# 03_RPiCM4.net
KiCad netlist of a schematic drawn in Altium Designer
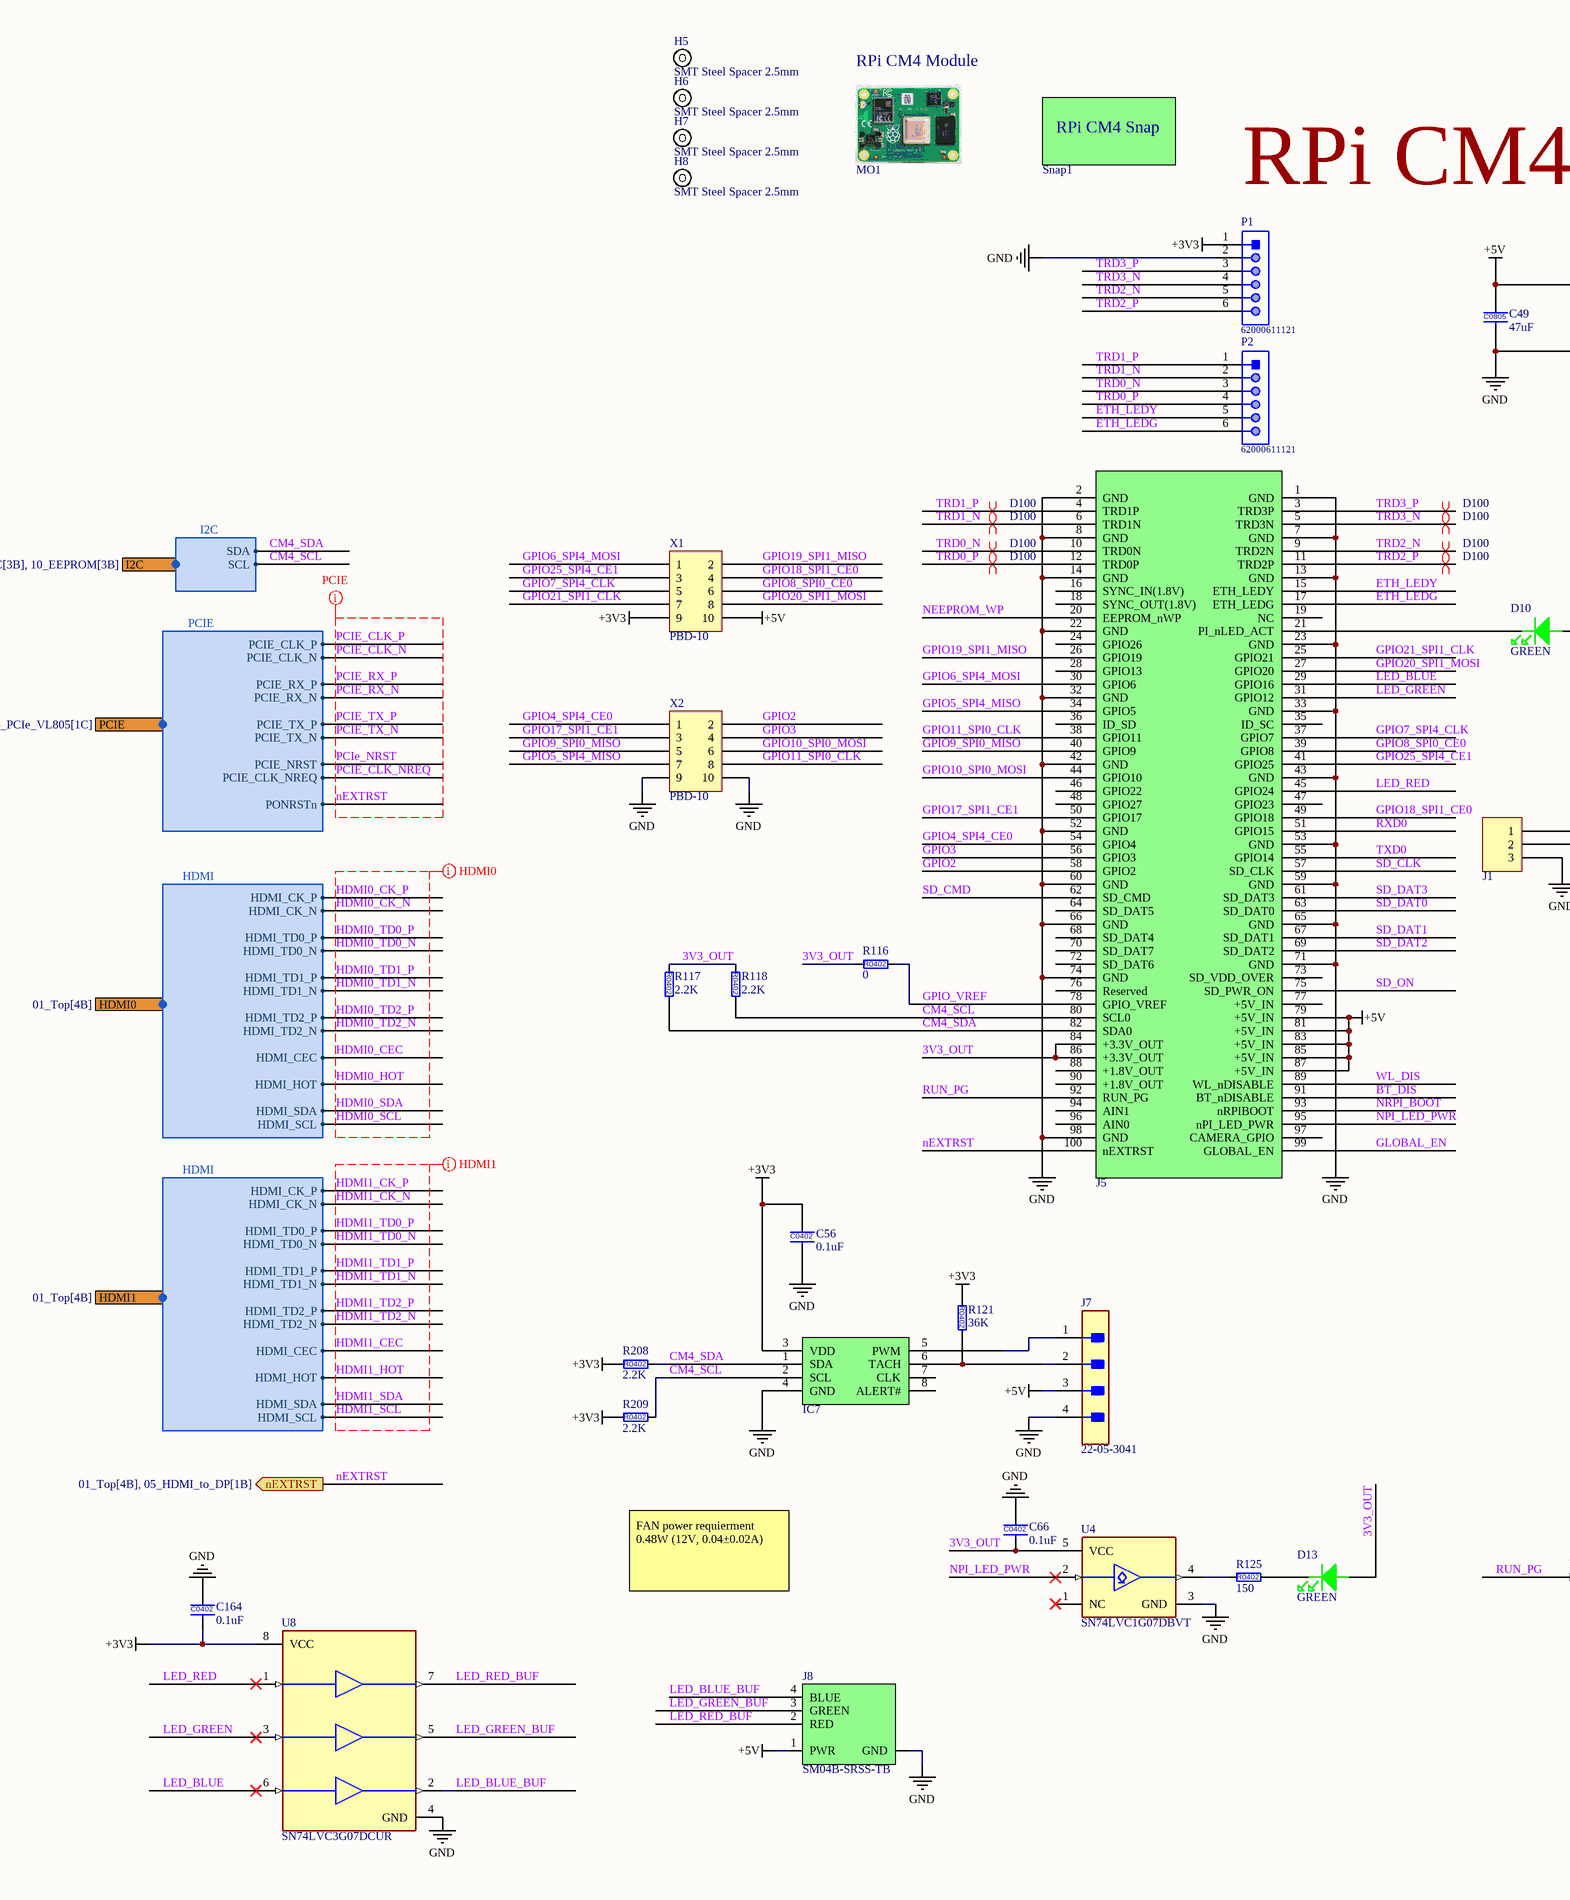
[diagram p0: 03_RPiCM4.SchDoc, left]
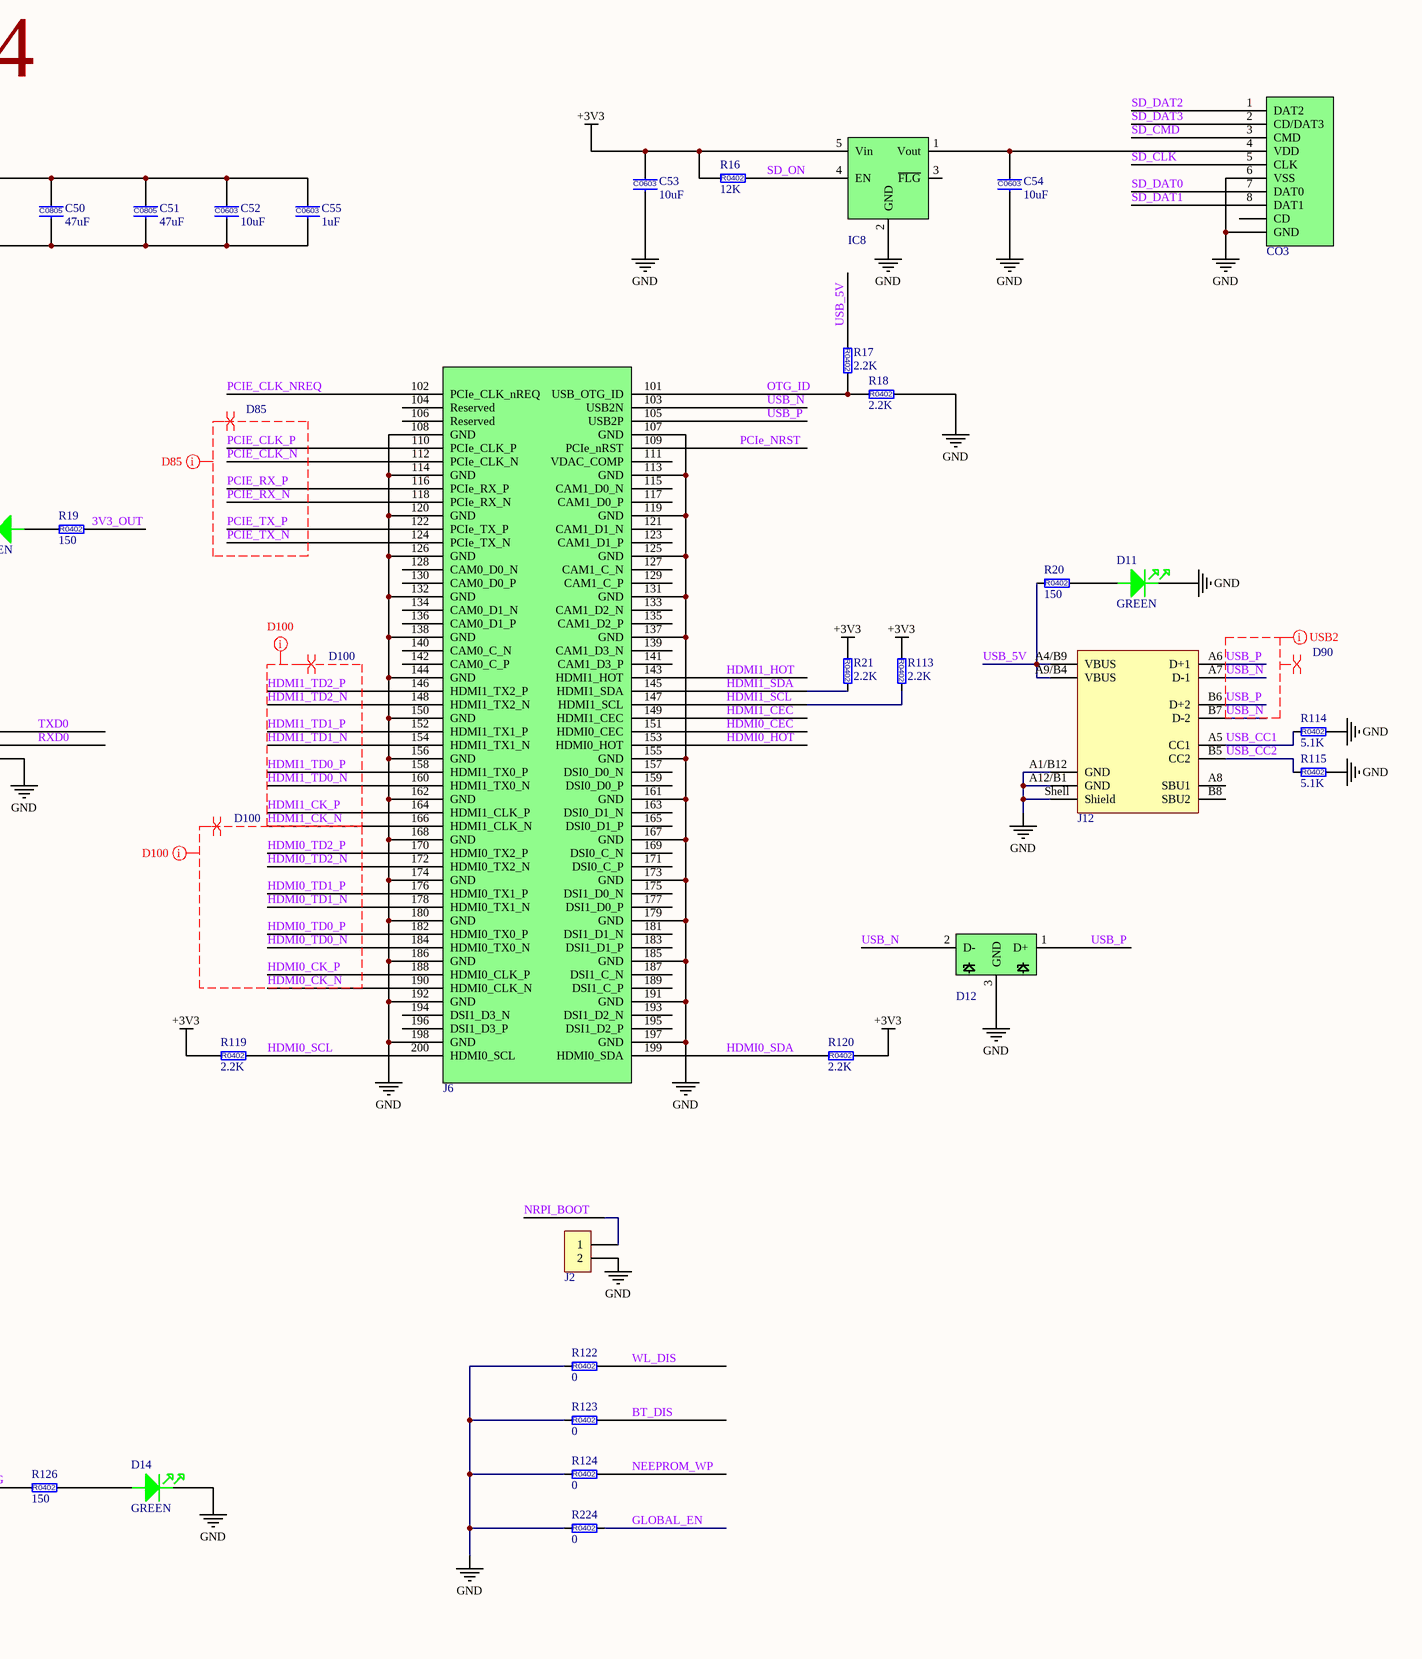
[diagram p1: 03_RPiCM4.SchDoc, right]

(export (version "E")
  (design (tool "Eeschema 10.0.6"))
  (components
    (comp (ref "C49")
      (value "47uF")
      (footprint "C0805")
      (description "CAP CER  47uF 20% 10V X5R 0805")
      (fields
        (field (name "MANUFACTURER") "KYOCERA AVX")
        (field (name "MANUFACTURER PART NUMBER") "0805ZD476MAT2A")
      )
      (libsource (lib "Capacitor") (part "0805ZD476MAT2A"))
    )
    (comp (ref "C50")
      (value "47uF")
      (footprint "C0805")
      (description "CAP CER  47uF 20% 10V X5R 0805")
      (fields
        (field (name "MANUFACTURER") "KYOCERA AVX")
        (field (name "MANUFACTURER PART NUMBER") "0805ZD476MAT2A")
      )
      (libsource (lib "Capacitor") (part "0805ZD476MAT2A"))
    )
    (comp (ref "C51")
      (value "47uF")
      (footprint "C0805")
      (description "CAP CER  47uF 20% 10V X5R 0805")
      (fields
        (field (name "MANUFACTURER") "KYOCERA AVX")
        (field (name "MANUFACTURER PART NUMBER") "0805ZD476MAT2A")
      )
      (libsource (lib "Capacitor") (part "0805ZD476MAT2A"))
    )
    (comp (ref "C52")
      (value "10uF")
      (footprint "C0603")
      (description "CAP CER 10uF 10% 10V X5R 0603")
      (fields
        (field (name "MANUFACTURER") "KYOCERA AVX")
        (field (name "MANUFACTURER PART NUMBER") "0603ZD106KAT2A")
      )
      (libsource (lib "Capacitor") (part "0603ZD106KAT2A"))
    )
    (comp (ref "C53")
      (value "10uF")
      (footprint "C0603")
      (description "CAP CER 10uF 10% 10V X5R 0603")
      (fields
        (field (name "MANUFACTURER") "KYOCERA AVX")
        (field (name "MANUFACTURER PART NUMBER") "0603ZD106KAT2A")
      )
      (libsource (lib "Capacitor") (part "0603ZD106KAT2A"))
    )
    (comp (ref "C54")
      (value "10uF")
      (footprint "C0603")
      (description "CAP CER 10uF 10% 10V X5R 0603")
      (fields
        (field (name "MANUFACTURER") "KYOCERA AVX")
        (field (name "MANUFACTURER PART NUMBER") "0603ZD106KAT2A")
      )
      (libsource (lib "Capacitor") (part "0603ZD106KAT2A"))
    )
    (comp (ref "C55")
      (value "1uF")
      (footprint "C0603")
      (description "CAP CER 1uF 20% 10V X5R 0603")
      (fields (field (name "TOLERANCE") "20%") (field (name "MANUFACTURER") "KYOCERA AVX"))
      (libsource (lib "Capacitor") (part "0201ZD105MAT2A"))
    )
    (comp (ref "C56")
      (value "0.1uF")
      (footprint "C0402")
      (description "CAP CER  0.1uF 10% 25V X5R 0402")
      (fields
        (field (name "MANUFACTURER") "AVX Corporation")
        (field (name "MANUFACTURER PART NUMBER") "04023D104KAT2A")
      )
      (libsource (lib "Capacitor") (part "04023D104KAT2A"))
    )
    (comp (ref "C66")
      (value "0.1uF")
      (footprint "C0402")
      (description "CAP CER  0.1uF 10% 25V X5R 0402")
      (fields
        (field (name "MANUFACTURER") "AVX Corporation")
        (field (name "MANUFACTURER PART NUMBER") "04023D104KAT2A")
      )
      (libsource (lib "Capacitor") (part "04023D104KAT2A"))
    )
    (comp (ref "C164")
      (value "0.1uF")
      (footprint "C0402")
      (description "CAP CER  0.1uF 10% 25V X5R 0402")
      (fields
        (field (name "MANUFACTURER") "AVX Corporation")
        (field (name "MANUFACTURER PART NUMBER") "04023D104KAT2A")
      )
      (libsource (lib "Capacitor") (part "04023D104KAT2A"))
    )
    (comp (ref "CO3")
      (value "µSD-Card")
      (footprint "693071030811")
      (description "Micro Sd Card, Push-Push, 8Pos, Smt Rohs Compliant: Yes")
      (fields (field (name "PART NUMBER") "CO0027") (field (name "MANUFACTURER") "Wurth Electronics"))
      (libsource (lib "new") (part "693071030811"))
    )
    (comp (ref "D10")
      (value "GREEN")
      (footprint "LED_0603")
      (description "LED Uni-Color Yellow Green 574nm 2-Pin Chip 0603(1608Metric) T/R")
      (fields
        (field (name "MANUFACTURER") "Vishay Semiconductors")
        (field (name "MANUFACTURER PART NUMBER") "VLMG1300-GS08")
      )
      (libsource (lib "led") (part "LED_SMD_0603_GREEN"))
    )
    (comp (ref "D11")
      (value "GREEN")
      (footprint "LED_0603")
      (description "LED Uni-Color Yellow Green 574nm 2-Pin Chip 0603(1608Metric) T/R")
      (fields
        (field (name "MANUFACTURER") "Vishay Semiconductors")
        (field (name "MANUFACTURER PART NUMBER") "VLMG1300-GS08")
      )
      (libsource (lib "led") (part "LED_SMD_0603_GREEN"))
    )
    (comp (ref "D12")
      (value "TPD2EUSB30DRTR")
      (footprint "TPD2EUSB30DRTR_SOT-3")
      (fields (field (name "MANUFACTURER") "Texas Instruments"))
      (libsource (lib "new") (part "TPD2EUSB30DRTR"))
    )
    (comp (ref "D13")
      (value "GREEN")
      (footprint "LED_0603")
      (description "LED Uni-Color Yellow Green 574nm 2-Pin Chip 0603(1608Metric) T/R")
      (fields
        (field (name "MANUFACTURER") "Vishay Semiconductors")
        (field (name "MANUFACTURER PART NUMBER") "VLMG1300-GS08")
      )
      (libsource (lib "led") (part "LED_SMD_0603_GREEN"))
    )
    (comp (ref "D14")
      (value "GREEN")
      (footprint "LED_0603")
      (description "LED Uni-Color Yellow Green 574nm 2-Pin Chip 0603(1608Metric) T/R")
      (fields
        (field (name "MANUFACTURER") "Vishay Semiconductors")
        (field (name "MANUFACTURER PART NUMBER") "VLMG1300-GS08")
      )
      (libsource (lib "led") (part "LED_SMD_0603_GREEN"))
    )
    (comp (ref "H5")
      (value "SMT Steel Spacer 2.5mm")
      (description "Spacer Material: Steel Mounting: SMT Series: WA-SMSI Thread D: M2.5")
      (fields
        (field (name "MANUFACTURER") "Wurth Electronics")
        (field (name "MANUFACTURER PART NUMBER") "9774030151R")
      )
      (libsource (lib "mechanical") (part "9774030151R"))
    )
    (comp (ref "H6")
      (value "SMT Steel Spacer 2.5mm")
      (description "Spacer Material: Steel Mounting: SMT Series: WA-SMSI Thread D: M2.5")
      (fields
        (field (name "MANUFACTURER") "Wurth Electronics")
        (field (name "MANUFACTURER PART NUMBER") "9774030151R")
      )
      (libsource (lib "mechanical") (part "9774030151R"))
    )
    (comp (ref "H7")
      (value "SMT Steel Spacer 2.5mm")
      (description "Spacer Material: Steel Mounting: SMT Series: WA-SMSI Thread D: M2.5")
      (fields
        (field (name "MANUFACTURER") "Wurth Electronics")
        (field (name "MANUFACTURER PART NUMBER") "9774030151R")
      )
      (libsource (lib "mechanical") (part "9774030151R"))
    )
    (comp (ref "H8")
      (value "SMT Steel Spacer 2.5mm")
      (description "Spacer Material: Steel Mounting: SMT Series: WA-SMSI Thread D: M2.5")
      (fields
        (field (name "MANUFACTURER") "Wurth Electronics")
        (field (name "MANUFACTURER PART NUMBER") "9774030151R")
      )
      (libsource (lib "mechanical") (part "9774030151R"))
    )
    (comp (ref "IC7")
      (value "EMC2301")
      (footprint "EMC2301-1-ACZL-TR_MSOP-8")
      (description "RPM-BASED PWM FAN CONTROLLER")
      (fields (field (name "PART NUMBER") "IC0054") (field (name "MANFACTPART") "EMC2301-1-ACZL-TR"))
      (libsource (lib "new") (part "EMC2301-1-ACZL-TR"))
    )
    (comp (ref "IC8")
      (value "RT9742")
      (footprint "RT9742GGJ5_SOT_23_5")
      (description "IC Pwr Swtch N-chan 1: 1 TSOT23-5")
      (fields (field (name "PART NUMBER") "IC0029") (field (name "MANFACTPART") "RT9742GGJ5"))
      (libsource (lib "new") (part "RT9742GGJ5"))
    )
    (comp (ref "J1")
      (value "PLS-3")
      (footprint "PLS-3-3D")
      (description "Board to Board Connector Straight Header Single Row 3 Position 2.54mm Pitch Through Hole Bag")
      (fields
        (field (name "MANUFACTURER") "Amphenol")
        (field (name "MANUFACTURER PART NUMBER") "G800W305018EU")
      )
      (libsource (lib "Connector") (part "PLS-3"))
    )
    (comp (ref "J2")
      (value "PLS-2")
      (footprint "PLS-2-3D")
      (description "Pin Header 2.54MM Pitch Str, 1X2PIN, Full G/f, NY6T, 6.1MM*2.5MM*3.0MM / Bag")
      (fields
        (field (name "MANUFACTURER") "Amphenol")
        (field (name "MANUFACTURER PART NUMBER") "G800W306018EU")
      )
      (libsource (lib "Connector") (part "PLS-2"))
    )
    (comp (ref "J5")
      (value "CM4-1")
      (footprint "CM4_CON_A")
      (description "0.4mm Pitch, 1.5-4.0mm Height, Board to Board / FPC to Board Connectors")
      (fields (field (name "PART NUMBER") "MO0012") (field (name "MANFACTPART") "DF40HC(3.0)-100DS-0.4V"))
      (libsource (lib "new") (part "CM4_module_A"))
    )
    (comp (ref "J6")
      (value "CM4-1")
      (footprint "CM4_Con_B")
      (description "0.4mm Pitch, 1.5-4.0mm Height, Board to Board / FPC to Board Connectors")
      (fields (field (name "PART NUMBER") "MO0012") (field (name "MANFACTPART") "DF40HC(3.0)-100DS-0.4V"))
      (libsource (lib "new") (part "CM4_module_B"))
    )
    (comp (ref "J7")
      (value "22-05-3041")
      (footprint "FP-22-05-3041-MFG")
      (description "KK 254 Solid Header, Right-Angle, with Friction Lock, 4 Circuits, Tin (Sn) Plating")
      (fields
        (field (name "OCTOPART") "https://octopart.com/22-05-3041-molex-2579")
        (field (name "MANUFACTURER") "Molex")
      )
      (libsource (lib "new") (part "22-05-3041"))
    )
    (comp (ref "J8")
      (value "SM04B-SRSS-TB")
      (footprint "SM04B")
      (description "CONN HEADER SH 4POS SIDE 1MM TIN")
      (fields (field (name "PART NUMBER") "CO0056") (field (name "MANUFACTURER") "JST"))
      (libsource (lib "new") (part "SM04B-SRSS-TB"))
    )
    (comp (ref "J12")
      (value "USB4105-GF-A")
      (footprint "USB4105-GF-A")
      (description "Conn USB 2.0 Type C RCP 24 POS 0.3mm/0.5mm Solder RA SMD 24 Terminal 1 Port T/R")
      (fields (field (name "MANUFACTURER") "Global Connector Technology"))
      (libsource (lib "new") (part "USB4105-GF-A"))
    )
    (comp (ref "MO1")
      (value "CM4_module")
      (footprint "CM4_step")
      (description "CM4 module")
      (fields (field (name "PART NUMBER") "MO0011") (field (name "MANFACTPART") "RPI CM4"))
      (libsource (lib "new") (part "CM4_module"))
    )
    (comp (ref "P1")
      (value "62000611121")
      (footprint "62000611121")
      (description "THT Vertical Pin Header WR-PHD, Pitch 2.00 mm, Single Row, 6 pins")
      (fields (field (name "MANUFACTURER") "Wurth Elektronik") (field (name "PUBLISHER") "WurthElektronik"))
      (libsource (lib "Pin_header") (part "CMP-1502-00960-1"))
    )
    (comp (ref "P2")
      (value "62000611121")
      (footprint "62000611121")
      (description "THT Vertical Pin Header WR-PHD, Pitch 2.00 mm, Single Row, 6 pins")
      (fields (field (name "MANUFACTURER") "Wurth Elektronik") (field (name "PUBLISHER") "WurthElektronik"))
      (libsource (lib "Pin_header") (part "CMP-1502-00960-1"))
    )
    (comp (ref "R16")
      (value "12K")
      (footprint "R0402")
      (description "RES SMD 12K ohm 1% 1/16W R0402")
      (fields
        (field (name "MANUFACTURER") "Vishay")
        (field (name "MANUFACTURER PART NUMBER") "CRCW040212K0FK")
      )
      (libsource (lib "Resistor") (part "CRCW040212K0FK"))
    )
    (comp (ref "R17")
      (value "2.2K")
      (footprint "R0402")
      (description "RES SMD 2.2K ohm 1% 1/16W R0402")
      (fields
        (field (name "MANUFACTURER") "Vishay")
        (field (name "MANUFACTURER PART NUMBER") "CRCW04022K20FK")
      )
      (libsource (lib "Resistor") (part "CRCW04022K20FK"))
    )
    (comp (ref "R18")
      (value "2.2K")
      (footprint "R0402")
      (description "RES SMD 2.2K ohm 1% 1/16W R0402")
      (fields
        (field (name "MANUFACTURER") "Vishay")
        (field (name "MANUFACTURER PART NUMBER") "CRCW04022K20FK")
      )
      (libsource (lib "Resistor") (part "CRCW04022K20FK"))
    )
    (comp (ref "R19")
      (value "150")
      (footprint "R0402")
      (description "RES SMD 150 ohm 1% 1/16W R0402")
      (fields
        (field (name "MANUFACTURER") "Vishay Dale")
        (field (name "MANUFACTURER PART NUMBER") "CRCW0402150RFKEDC")
      )
      (libsource (lib "Resistor") (part "CRCW0402150RFKEDC"))
    )
    (comp (ref "R20")
      (value "150")
      (footprint "R0402")
      (description "RES SMD 150 ohm 1% 1/16W R0402")
      (fields
        (field (name "MANUFACTURER") "Vishay Dale")
        (field (name "MANUFACTURER PART NUMBER") "CRCW0402150RFKEDC")
      )
      (libsource (lib "Resistor") (part "CRCW0402150RFKEDC"))
    )
    (comp (ref "R21")
      (value "2.2K")
      (footprint "R0402")
      (description "RES SMD 2.2K ohm 1% 1/16W R0402")
      (fields
        (field (name "MANUFACTURER") "Vishay")
        (field (name "MANUFACTURER PART NUMBER") "CRCW04022K20FK")
      )
      (libsource (lib "Resistor") (part "CRCW04022K20FK"))
    )
    (comp (ref "R113")
      (value "2.2K")
      (footprint "R0402")
      (description "RES SMD 2.2K ohm 1% 1/16W R0402")
      (fields
        (field (name "MANUFACTURER") "Vishay")
        (field (name "MANUFACTURER PART NUMBER") "CRCW04022K20FK")
      )
      (libsource (lib "Resistor") (part "CRCW04022K20FK"))
    )
    (comp (ref "R114")
      (value "5.1K")
      (footprint "R0402")
      (description "RES SMD 5.1K ohm 1% 1/16W R0402")
      (fields
        (field (name "MANUFACTURER") "Vishay")
        (field (name "MANUFACTURER PART NUMBER") "CRCW04025K10FK")
      )
      (libsource (lib "Resistor") (part "CRCW04025K10FK"))
    )
    (comp (ref "R115")
      (value "5.1K")
      (footprint "R0402")
      (description "RES SMD 5.1K ohm 1% 1/16W R0402")
      (fields
        (field (name "MANUFACTURER") "Vishay")
        (field (name "MANUFACTURER PART NUMBER") "CRCW04025K10FK")
      )
      (libsource (lib "Resistor") (part "CRCW04025K10FK"))
    )
    (comp (ref "R116")
      (value "0")
      (footprint "R0402")
      (description "RES SMD 0 ohm 1/16W R0402")
      (fields
        (field (name "MANUFACTURER") "Vishay Dale")
        (field (name "MANUFACTURER PART NUMBER") "CRCW04020000Z0")
      )
      (libsource (lib "Resistor") (part "CRCW04020000Z0"))
    )
    (comp (ref "R117")
      (value "2.2K")
      (footprint "R0402")
      (description "RES SMD 2.2K ohm 1% 1/16W R0402")
      (fields
        (field (name "MANUFACTURER") "Vishay")
        (field (name "MANUFACTURER PART NUMBER") "CRCW04022K20FK")
      )
      (libsource (lib "Resistor") (part "CRCW04022K20FK"))
    )
    (comp (ref "R118")
      (value "2.2K")
      (footprint "R0402")
      (description "RES SMD 2.2K ohm 1% 1/16W R0402")
      (fields
        (field (name "MANUFACTURER") "Vishay")
        (field (name "MANUFACTURER PART NUMBER") "CRCW04022K20FK")
      )
      (libsource (lib "Resistor") (part "CRCW04022K20FK"))
    )
    (comp (ref "R119")
      (value "2.2K")
      (footprint "R0402")
      (description "RES SMD 2.2K ohm 1% 1/16W R0402")
      (fields
        (field (name "MANUFACTURER") "Vishay")
        (field (name "MANUFACTURER PART NUMBER") "CRCW04022K20FK")
      )
      (libsource (lib "Resistor") (part "CRCW04022K20FK"))
    )
    (comp (ref "R120")
      (value "2.2K")
      (footprint "R0402")
      (description "RES SMD 2.2K ohm 1% 1/16W R0402")
      (fields
        (field (name "MANUFACTURER") "Vishay")
        (field (name "MANUFACTURER PART NUMBER") "CRCW04022K20FK")
      )
      (libsource (lib "Resistor") (part "CRCW04022K20FK"))
    )
    (comp (ref "R121")
      (value "36K")
      (footprint "R0402")
      (description "RES SMD 36K ohm 1% 1/16W R0402")
      (fields
        (field (name "MANUFACTURER") "Vishay")
        (field (name "MANUFACTURER PART NUMBER") "CRCW040236K0FK")
      )
      (libsource (lib "Resistor") (part "CRCW040236K0FK"))
    )
    (comp (ref "R122")
      (value "0")
      (footprint "R0402")
      (description "RES SMD 0 ohm 1/16W R0402")
      (fields
        (field (name "MANUFACTURER") "Vishay Dale")
        (field (name "MANUFACTURER PART NUMBER") "CRCW04020000Z0")
      )
      (libsource (lib "Resistor") (part "CRCW04020000Z0"))
    )
    (comp (ref "R123")
      (value "0")
      (footprint "R0402")
      (description "RES SMD 0 ohm 1/16W R0402")
      (fields
        (field (name "MANUFACTURER") "Vishay Dale")
        (field (name "MANUFACTURER PART NUMBER") "CRCW04020000Z0")
      )
      (libsource (lib "Resistor") (part "CRCW04020000Z0"))
    )
    (comp (ref "R124")
      (value "0")
      (footprint "R0402")
      (description "RES SMD 0 ohm 1/16W R0402")
      (fields
        (field (name "MANUFACTURER") "Vishay Dale")
        (field (name "MANUFACTURER PART NUMBER") "CRCW04020000Z0")
      )
      (libsource (lib "Resistor") (part "CRCW04020000Z0"))
    )
    (comp (ref "R125")
      (value "150")
      (footprint "R0402")
      (description "RES SMD 150 ohm 1% 1/16W R0402")
      (fields
        (field (name "MANUFACTURER") "Vishay Dale")
        (field (name "MANUFACTURER PART NUMBER") "CRCW0402150RFKEDC")
      )
      (libsource (lib "Resistor") (part "CRCW0402150RFKEDC"))
    )
    (comp (ref "R126")
      (value "150")
      (footprint "R0402")
      (description "RES SMD 150 ohm 1% 1/16W R0402")
      (fields
        (field (name "MANUFACTURER") "Vishay Dale")
        (field (name "MANUFACTURER PART NUMBER") "CRCW0402150RFKEDC")
      )
      (libsource (lib "Resistor") (part "CRCW0402150RFKEDC"))
    )
    (comp (ref "R208")
      (value "2.2K")
      (footprint "R0402")
      (description "RES SMD 2.2K ohm 1% 1/16W R0402")
      (fields
        (field (name "MANUFACTURER") "Vishay")
        (field (name "MANUFACTURER PART NUMBER") "CRCW04022K20FK")
      )
      (libsource (lib "Resistor") (part "CRCW04022K20FK"))
    )
    (comp (ref "R209")
      (value "2.2K")
      (footprint "R0402")
      (description "RES SMD 2.2K ohm 1% 1/16W R0402")
      (fields
        (field (name "MANUFACTURER") "Vishay")
        (field (name "MANUFACTURER PART NUMBER") "CRCW04022K20FK")
      )
      (libsource (lib "Resistor") (part "CRCW04022K20FK"))
    )
    (comp (ref "R224")
      (value "0")
      (footprint "R0402")
      (description "RES SMD 0 ohm 1/16W R0402")
      (fields
        (field (name "MANUFACTURER") "Vishay Dale")
        (field (name "MANUFACTURER PART NUMBER") "CRCW04020000Z0")
      )
      (libsource (lib "Resistor") (part "CRCW04020000Z0"))
    )
    (comp (ref "Snap1")
      (value "CM4-1")
      (footprint "CM4_snap")
      (description "RPI CM4 snap")
      (fields (field (name "PART NUMBER") "MO0012"))
      (libsource (lib "new") (part "CM4_snap"))
    )
    (comp (ref "U4")
      (value "SN74LVC1G07DBVT")
      (footprint "SN74LVC1G07DBVT_SOT_23_5")
      (description "Single 1.65-V to 5.5-V buffer with open-drain outputs 5-SOT-23 -40 to 125")
      (fields
        (field (name "MANUFACTURER") "Texas Instruments")
        (field (name "OCTOPART") "https://octopart.com/sn74lvc1g07dbvt-texas+instruments-1006798")
      )
      (libsource (lib "new") (part "SN74LVC1G07DBVT"))
    )
    (comp (ref "U8")
      (value "SN74LVC3G07DCUR")
      (footprint "SN74LVC3G07DCUR_VSSOP_8")
      (description "Buffer/Driver 3-CH Non-Inverting Open Drain CMOS 8-Pin VSSOP T/R")
      (fields (field (name "MANUFACTURER") "Texas Instruments"))
      (libsource (lib "ic") (part "SN74LVC3G07DCUR"))
    )
    (comp (ref "X1")
      (value "PBD-10")
      (footprint "PXD-10")
      (description "Header, 5-Pin, Dual row")
      (libsource (lib "Connector") (part "PBD-10"))
    )
    (comp (ref "X2")
      (value "PBD-10")
      (footprint "PXD-10")
      (description "Header, 5-Pin, Dual row")
      (libsource (lib "Connector") (part "PBD-10"))
    )
  )
  (nets
    (net (code "4") (name "+3V3") (class "Default")
      (node (ref "C164") (pin "2") (pinfunction "2_2") (pintype "passive"))
      (node (ref "C53") (pin "1") (pinfunction "1_1") (pintype "passive"))
      (node (ref "C56") (pin "1") (pinfunction "1_1") (pintype "passive"))
      (node (ref "IC7") (pin "3") (pinfunction "VDD_3") (pintype "passive"))
      (node (ref "IC8") (pin "5") (pinfunction "Vin_5") (pintype "power_in"))
      (node (ref "P1") (pin "1") (pinfunction "1_1") (pintype "passive"))
      (node (ref "R113") (pin "1") (pinfunction "1_1") (pintype "passive"))
      (node (ref "R119") (pin "1") (pinfunction "1_1") (pintype "passive"))
      (node (ref "R120") (pin "2") (pinfunction "2_2") (pintype "passive"))
      (node (ref "R121") (pin "1") (pinfunction "1_1") (pintype "passive"))
      (node (ref "R16") (pin "1") (pinfunction "1_1") (pintype "passive"))
      (node (ref "R208") (pin "1") (pinfunction "1_1") (pintype "passive"))
      (node (ref "R209") (pin "1") (pinfunction "1_1") (pintype "passive"))
      (node (ref "R21") (pin "1") (pinfunction "1_1") (pintype "passive"))
      (node (ref "U8") (pin "8") (pinfunction "VCC_8") (pintype "power_in"))
      (node (ref "X1") (pin "9") (pinfunction "9_9") (pintype "passive"))
    )
    (net (code "5") (name "+5V") (class "Default")
      (node (ref "C49") (pin "1") (pinfunction "1_1") (pintype "passive"))
      (node (ref "C50") (pin "1") (pinfunction "1_1") (pintype "passive"))
      (node (ref "C51") (pin "1") (pinfunction "1_1") (pintype "passive"))
      (node (ref "C52") (pin "1") (pinfunction "1_1") (pintype "passive"))
      (node (ref "C55") (pin "1") (pinfunction "1_1") (pintype "passive"))
      (node (ref "J5") (pin "79") (pinfunction "+5V_IN_79") (pintype "passive"))
      (node (ref "J5") (pin "81") (pinfunction "+5V_IN_81") (pintype "passive"))
      (node (ref "J5") (pin "83") (pinfunction "+5V_IN_83") (pintype "passive"))
      (node (ref "J5") (pin "85") (pinfunction "+5V_IN_85") (pintype "passive"))
      (node (ref "J5") (pin "87") (pinfunction "+5V_IN_87") (pintype "passive"))
      (node (ref "J7") (pin "3") (pinfunction "3_3") (pintype "passive"))
      (node (ref "J8") (pin "1") (pinfunction "PWR_1") (pintype "power_in"))
      (node (ref "X1") (pin "10") (pinfunction "10_10") (pintype "passive"))
    )
    (net (code "6") (name "/3V3_OUT") (class "Default")
      (node (ref "C66") (pin "2") (pinfunction "2_2") (pintype "passive"))
      (node (ref "D13") (pin "2") (pinfunction "Anode_2") (pintype "passive"))
      (node (ref "J5") (pin "84") (pinfunction "+3.3V_OUT_84") (pintype "passive"))
      (node (ref "J5") (pin "86") (pinfunction "+3.3V_OUT_86") (pintype "passive"))
      (node (ref "R116") (pin "1") (pinfunction "1_1") (pintype "passive"))
      (node (ref "R117") (pin "1") (pinfunction "1_1") (pintype "passive"))
      (node (ref "R118") (pin "1") (pinfunction "1_1") (pintype "passive"))
      (node (ref "R19") (pin "2") (pinfunction "2_2") (pintype "passive"))
      (node (ref "U4") (pin "5") (pinfunction "VCC_5") (pintype "power_in"))
    )
    (net (code "7") (name "/BT_DIS") (class "Default")
      (node (ref "J5") (pin "91") (pinfunction "BT_nDISABLE_91") (pintype "passive"))
      (node (ref "R123") (pin "2") (pinfunction "2_2") (pintype "passive"))
    )
    (net (code "8") (name "/CM4_SCL") (class "Default")
      (node (ref "IC7") (pin "2") (pinfunction "SCL_2") (pintype "passive"))
      (node (ref "J5") (pin "80") (pinfunction "SCL0_80") (pintype "passive"))
      (node (ref "R118") (pin "2") (pinfunction "2_2") (pintype "passive"))
      (node (ref "R209") (pin "2") (pinfunction "2_2") (pintype "passive"))
    )
    (net (code "9") (name "/CM4_SDA") (class "Default")
      (node (ref "IC7") (pin "1") (pinfunction "SDA_1") (pintype "passive"))
      (node (ref "J5") (pin "82") (pinfunction "SDA0_82") (pintype "passive"))
      (node (ref "R117") (pin "2") (pinfunction "2_2") (pintype "passive"))
      (node (ref "R208") (pin "2") (pinfunction "2_2") (pintype "passive"))
    )
    (net (code "10") (name "/ETH_LEDG") (class "Default")
      (node (ref "J5") (pin "17") (pinfunction "ETH_LEDG_17") (pintype "passive"))
      (node (ref "P2") (pin "6") (pinfunction "6_6") (pintype "passive"))
    )
    (net (code "11") (name "/ETH_LEDY") (class "Default")
      (node (ref "J5") (pin "15") (pinfunction "ETH_LEDY_15") (pintype "passive"))
      (node (ref "P2") (pin "5") (pinfunction "5_5") (pintype "passive"))
    )
    (net (code "12") (name "/GLOBAL_EN") (class "Default")
      (node (ref "J5") (pin "99") (pinfunction "GLOBAL_EN_99") (pintype "passive"))
      (node (ref "R224") (pin "2") (pinfunction "2_2") (pintype "passive"))
    )
    (net (code "13") (name "/GPIO2") (class "Default")
      (node (ref "J5") (pin "58") (pinfunction "GPIO2_58") (pintype "passive"))
      (node (ref "X2") (pin "2") (pinfunction "2_2") (pintype "passive"))
    )
    (net (code "14") (name "/GPIO3") (class "Default")
      (node (ref "J5") (pin "56") (pinfunction "GPIO3_56") (pintype "passive"))
      (node (ref "X2") (pin "4") (pinfunction "4_4") (pintype "passive"))
    )
    (net (code "15") (name "/GPIO4_SPI4_CE0") (class "Default")
      (node (ref "J5") (pin "54") (pinfunction "GPIO4_54") (pintype "passive"))
      (node (ref "X2") (pin "1") (pinfunction "1_1") (pintype "passive"))
    )
    (net (code "16") (name "/GPIO5_SPI4_MISO") (class "Default")
      (node (ref "J5") (pin "34") (pinfunction "GPIO5_34") (pintype "passive"))
      (node (ref "X2") (pin "7") (pinfunction "7_7") (pintype "passive"))
    )
    (net (code "17") (name "/GPIO6_SPI4_MOSI") (class "Default")
      (node (ref "J5") (pin "30") (pinfunction "GPIO6_30") (pintype "passive"))
      (node (ref "X1") (pin "1") (pinfunction "1_1") (pintype "passive"))
    )
    (net (code "18") (name "/GPIO7_SPI4_CLK") (class "Default")
      (node (ref "J5") (pin "37") (pinfunction "GPIO7_37") (pintype "passive"))
      (node (ref "X1") (pin "5") (pinfunction "5_5") (pintype "passive"))
    )
    (net (code "19") (name "/GPIO8_SPI0_CE0") (class "Default")
      (node (ref "J5") (pin "39") (pinfunction "GPIO8_39") (pintype "passive"))
      (node (ref "X1") (pin "6") (pinfunction "6_6") (pintype "passive"))
    )
    (net (code "20") (name "/GPIO9_SPI0_MISO") (class "Default")
      (node (ref "J5") (pin "40") (pinfunction "GPIO9_40") (pintype "passive"))
      (node (ref "X2") (pin "5") (pinfunction "5_5") (pintype "passive"))
    )
    (net (code "21") (name "/GPIO10_SPI0_MOSI") (class "Default")
      (node (ref "J5") (pin "44") (pinfunction "GPIO10_44") (pintype "passive"))
      (node (ref "X2") (pin "6") (pinfunction "6_6") (pintype "passive"))
    )
    (net (code "22") (name "/GPIO11_SPI0_CLK") (class "Default")
      (node (ref "J5") (pin "38") (pinfunction "GPIO11_38") (pintype "passive"))
      (node (ref "X2") (pin "8") (pinfunction "8_8") (pintype "passive"))
    )
    (net (code "23") (name "/GPIO17_SPI1_CE1") (class "Default")
      (node (ref "J5") (pin "50") (pinfunction "GPIO17_50") (pintype "passive"))
      (node (ref "X2") (pin "3") (pinfunction "3_3") (pintype "passive"))
    )
    (net (code "24") (name "/GPIO18_SPI1_CE0") (class "Default")
      (node (ref "J5") (pin "49") (pinfunction "GPIO18_49") (pintype "passive"))
      (node (ref "X1") (pin "4") (pinfunction "4_4") (pintype "passive"))
    )
    (net (code "25") (name "/GPIO19_SPI1_MISO") (class "Default")
      (node (ref "J5") (pin "26") (pinfunction "GPIO19_26") (pintype "passive"))
      (node (ref "X1") (pin "2") (pinfunction "2_2") (pintype "passive"))
    )
    (net (code "26") (name "/GPIO20_SPI1_MOSI") (class "Default")
      (node (ref "J5") (pin "27") (pinfunction "GPIO20_27") (pintype "passive"))
      (node (ref "X1") (pin "8") (pinfunction "8_8") (pintype "passive"))
    )
    (net (code "27") (name "/GPIO21_SPI1_CLK") (class "Default")
      (node (ref "J5") (pin "25") (pinfunction "GPIO21_25") (pintype "passive"))
      (node (ref "X1") (pin "7") (pinfunction "7_7") (pintype "passive"))
    )
    (net (code "28") (name "/GPIO25_SPI4_CE1") (class "Default")
      (node (ref "J5") (pin "41") (pinfunction "GPIO25_41") (pintype "passive"))
      (node (ref "X1") (pin "3") (pinfunction "3_3") (pintype "passive"))
    )
    (net (code "29") (name "/GPIO_VREF") (class "Default")
      (node (ref "J5") (pin "78") (pinfunction "GPIO_VREF_78") (pintype "passive"))
      (node (ref "R116") (pin "2") (pinfunction "2_2") (pintype "passive"))
    )
    (net (code "30") (name "/HDMI0_CEC") (class "Default")
      (node (ref "J6") (pin "151") (pinfunction "HDMI0_CEC_151") (pintype "passive"))
    )
    (net (code "31") (name "/HDMI0_CK_N") (class "Default")
      (node (ref "J6") (pin "190") (pinfunction "HDMI0_CLK_N_190") (pintype "passive"))
    )
    (net (code "32") (name "/HDMI0_CK_P") (class "Default")
      (node (ref "J6") (pin "188") (pinfunction "HDMI0_CLK_P_188") (pintype "passive"))
    )
    (net (code "33") (name "/HDMI0_HOT") (class "Default")
      (node (ref "J6") (pin "153") (pinfunction "HDMI0_HOT_153") (pintype "passive"))
    )
    (net (code "34") (name "/HDMI0_SCL") (class "Default")
      (node (ref "J6") (pin "200") (pinfunction "HDMI0_SCL_200") (pintype "passive"))
      (node (ref "R119") (pin "2") (pinfunction "2_2") (pintype "passive"))
    )
    (net (code "35") (name "/HDMI0_SDA") (class "Default")
      (node (ref "J6") (pin "199") (pinfunction "HDMI0_SDA_199") (pintype "passive"))
      (node (ref "R120") (pin "1") (pinfunction "1_1") (pintype "passive"))
    )
    (net (code "36") (name "/HDMI0_TD0_N") (class "Default")
      (node (ref "J6") (pin "184") (pinfunction "HDMI0_TX0_N_184") (pintype "passive"))
    )
    (net (code "37") (name "/HDMI0_TD0_P") (class "Default")
      (node (ref "J6") (pin "182") (pinfunction "HDMI0_TX0_P_182") (pintype "passive"))
    )
    (net (code "38") (name "/HDMI0_TD1_N") (class "Default")
      (node (ref "J6") (pin "178") (pinfunction "HDMI0_TX1_N_178") (pintype "passive"))
    )
    (net (code "39") (name "/HDMI0_TD1_P") (class "Default")
      (node (ref "J6") (pin "176") (pinfunction "HDMI0_TX1_P_176") (pintype "passive"))
    )
    (net (code "40") (name "/HDMI0_TD2_N") (class "Default")
      (node (ref "J6") (pin "172") (pinfunction "HDMI0_TX2_N_172") (pintype "passive"))
    )
    (net (code "41") (name "/HDMI0_TD2_P") (class "Default")
      (node (ref "J6") (pin "170") (pinfunction "HDMI0_TX2_P_170") (pintype "passive"))
    )
    (net (code "42") (name "/HDMI1_CEC") (class "Default")
      (node (ref "J6") (pin "149") (pinfunction "HDMI1_CEC_149") (pintype "passive"))
    )
    (net (code "43") (name "/HDMI1_CK_N") (class "Default")
      (node (ref "J6") (pin "166") (pinfunction "HDMI1_CLK_N_166") (pintype "passive"))
    )
    (net (code "44") (name "/HDMI1_CK_P") (class "Default")
      (node (ref "J6") (pin "164") (pinfunction "HDMI1_CLK_P_164") (pintype "passive"))
    )
    (net (code "45") (name "/HDMI1_HOT") (class "Default")
      (node (ref "J6") (pin "143") (pinfunction "HDMI1_HOT_143") (pintype "passive"))
    )
    (net (code "46") (name "/HDMI1_SCL") (class "Default")
      (node (ref "J6") (pin "147") (pinfunction "HDMI1_SCL_147") (pintype "passive"))
      (node (ref "R113") (pin "2") (pinfunction "2_2") (pintype "passive"))
    )
    (net (code "47") (name "/HDMI1_SDA") (class "Default")
      (node (ref "J6") (pin "145") (pinfunction "HDMI1_SDA_145") (pintype "passive"))
      (node (ref "R21") (pin "2") (pinfunction "2_2") (pintype "passive"))
    )
    (net (code "48") (name "/HDMI1_TD0_N") (class "Default")
      (node (ref "J6") (pin "160") (pinfunction "HDMI1_TX0_N_160") (pintype "passive"))
    )
    (net (code "49") (name "/HDMI1_TD0_P") (class "Default")
      (node (ref "J6") (pin "158") (pinfunction "HDMI1_TX0_P_158") (pintype "passive"))
    )
    (net (code "50") (name "/HDMI1_TD1_N") (class "Default")
      (node (ref "J6") (pin "154") (pinfunction "HDMI1_TX1_N_154") (pintype "passive"))
    )
    (net (code "51") (name "/HDMI1_TD1_P") (class "Default")
      (node (ref "J6") (pin "152") (pinfunction "HDMI1_TX1_P_152") (pintype "passive"))
    )
    (net (code "52") (name "/HDMI1_TD2_N") (class "Default")
      (node (ref "J6") (pin "148") (pinfunction "HDMI1_TX2_N_148") (pintype "passive"))
    )
    (net (code "53") (name "/HDMI1_TD2_P") (class "Default")
      (node (ref "J6") (pin "146") (pinfunction "HDMI1_TX2_P_146") (pintype "passive"))
    )
    (net (code "54") (name "/LED_BLUE") (class "Default")
      (node (ref "J5") (pin "29") (pinfunction "GPIO16_29") (pintype "passive"))
      (node (ref "U8") (pin "6") (pinfunction "3A_6") (pintype "input"))
    )
    (net (code "55") (name "/LED_BLUE_BUF") (class "Default")
      (node (ref "J8") (pin "4") (pinfunction "BLUE_4") (pintype "passive"))
      (node (ref "U8") (pin "2") (pinfunction "3Y_2") (pintype "output"))
    )
    (net (code "56") (name "/LED_GREEN") (class "Default")
      (node (ref "J5") (pin "31") (pinfunction "GPIO12_31") (pintype "passive"))
      (node (ref "U8") (pin "3") (pinfunction "2A_3") (pintype "input"))
    )
    (net (code "57") (name "/LED_GREEN_BUF") (class "Default")
      (node (ref "J8") (pin "3") (pinfunction "GREEN_3") (pintype "passive"))
      (node (ref "U8") (pin "5") (pinfunction "2Y_5") (pintype "output"))
    )
    (net (code "58") (name "/LED_RED") (class "Default")
      (node (ref "J5") (pin "45") (pinfunction "GPIO24_45") (pintype "passive"))
      (node (ref "U8") (pin "1") (pinfunction "1A_1") (pintype "input"))
    )
    (net (code "59") (name "/LED_RED_BUF") (class "Default")
      (node (ref "J8") (pin "2") (pinfunction "RED_2") (pintype "passive"))
      (node (ref "U8") (pin "7") (pinfunction "1Y_7") (pintype "output"))
    )
    (net (code "60") (name "/NEEPROM_WP") (class "Default")
      (node (ref "J5") (pin "20") (pinfunction "EEPROM_nWP_20") (pintype "passive"))
      (node (ref "R124") (pin "2") (pinfunction "2_2") (pintype "passive"))
    )
    (net (code "61") (name "/NPI_LED_PWR") (class "Default")
      (node (ref "J5") (pin "95") (pinfunction "nPI_LED_PWR_95") (pintype "passive"))
      (node (ref "U4") (pin "2") (pinfunction "A_2") (pintype "input"))
    )
    (net (code "62") (name "/NRPI_BOOT") (class "Default")
      (node (ref "J2") (pin "1") (pinfunction "1_1") (pintype "passive"))
      (node (ref "J5") (pin "93") (pinfunction "nRPIBOOT_93") (pintype "passive"))
    )
    (net (code "63") (name "/OTG_ID") (class "Default")
      (node (ref "J6") (pin "101") (pinfunction "USB_OTG_ID_101") (pintype "passive"))
      (node (ref "R17") (pin "2") (pinfunction "2_2") (pintype "passive"))
      (node (ref "R18") (pin "1") (pinfunction "1_1") (pintype "passive"))
    )
    (net (code "64") (name "/PCIE_CLK_N") (class "Default")
      (node (ref "J6") (pin "112") (pinfunction "PCIe_CLK_N_112") (pintype "passive"))
    )
    (net (code "65") (name "/PCIE_CLK_NREQ") (class "Default")
      (node (ref "J6") (pin "102") (pinfunction "PCIe_CLK_nREQ_102") (pintype "passive"))
    )
    (net (code "66") (name "/PCIE_CLK_P") (class "Default")
      (node (ref "J6") (pin "110") (pinfunction "PCIe_CLK_P_110") (pintype "passive"))
    )
    (net (code "67") (name "/PCIE_RX_N") (class "Default")
      (node (ref "J6") (pin "118") (pinfunction "PCIe_RX_N_118") (pintype "passive"))
    )
    (net (code "68") (name "/PCIE_RX_P") (class "Default")
      (node (ref "J6") (pin "116") (pinfunction "PCIe_RX_P_116") (pintype "passive"))
    )
    (net (code "69") (name "/PCIE_TX_N") (class "Default")
      (node (ref "J6") (pin "124") (pinfunction "PCIe_TX_N_124") (pintype "passive"))
    )
    (net (code "70") (name "/PCIE_TX_P") (class "Default")
      (node (ref "J6") (pin "122") (pinfunction "PCIe_TX_P_122") (pintype "passive"))
    )
    (net (code "71") (name "/PCIe_NRST") (class "Default")
      (node (ref "J6") (pin "109") (pinfunction "PCIe_nRST_109") (pintype "passive"))
    )
    (net (code "72") (name "/RUN_PG") (class "Default")
      (node (ref "J5") (pin "92") (pinfunction "RUN_PG_92") (pintype "passive"))
      (node (ref "R126") (pin "1") (pinfunction "1_1") (pintype "passive"))
    )
    (net (code "73") (name "/RXD0") (class "Default")
      (node (ref "J1") (pin "2") (pinfunction "2_2") (pintype "passive"))
      (node (ref "J5") (pin "51") (pinfunction "GPIO15_51") (pintype "passive"))
    )
    (net (code "74") (name "/SD_CLK") (class "Default")
      (node (ref "CO3") (pin "5") (pinfunction "CLK_5") (pintype "passive"))
      (node (ref "J5") (pin "57") (pinfunction "SD_CLK_57") (pintype "passive"))
    )
    (net (code "75") (name "/SD_CMD") (class "Default")
      (node (ref "CO3") (pin "3") (pinfunction "CMD_3") (pintype "passive"))
      (node (ref "J5") (pin "62") (pinfunction "SD_CMD_62") (pintype "passive"))
    )
    (net (code "76") (name "/SD_DAT0") (class "Default")
      (node (ref "CO3") (pin "7") (pinfunction "DAT0_7") (pintype "passive"))
      (node (ref "J5") (pin "63") (pinfunction "SD_DAT0_63") (pintype "passive"))
    )
    (net (code "77") (name "/SD_DAT1") (class "Default")
      (node (ref "CO3") (pin "8") (pinfunction "DAT1_8") (pintype "passive"))
      (node (ref "J5") (pin "67") (pinfunction "SD_DAT1_67") (pintype "passive"))
    )
    (net (code "78") (name "/SD_DAT2") (class "Default")
      (node (ref "CO3") (pin "1") (pinfunction "DAT2_1") (pintype "passive"))
      (node (ref "J5") (pin "69") (pinfunction "SD_DAT2_69") (pintype "passive"))
    )
    (net (code "79") (name "/SD_DAT3") (class "Default")
      (node (ref "CO3") (pin "2") (pinfunction "CD/DAT3_2") (pintype "passive"))
      (node (ref "J5") (pin "61") (pinfunction "SD_DAT3_61") (pintype "passive"))
    )
    (net (code "80") (name "/SD_ON") (class "Default")
      (node (ref "IC8") (pin "4") (pinfunction "EN_4") (pintype "power_in"))
      (node (ref "J5") (pin "75") (pinfunction "SD_PWR_ON_75") (pintype "passive"))
      (node (ref "R16") (pin "2") (pinfunction "2_2") (pintype "passive"))
    )
    (net (code "81") (name "/TRD0_N") (class "Default")
      (node (ref "J5") (pin "10") (pinfunction "TRD0N_10") (pintype "passive"))
      (node (ref "P2") (pin "3") (pinfunction "3_3") (pintype "passive"))
    )
    (net (code "82") (name "/TRD0_P") (class "Default")
      (node (ref "J5") (pin "12") (pinfunction "TRD0P_12") (pintype "passive"))
      (node (ref "P2") (pin "4") (pinfunction "4_4") (pintype "passive"))
    )
    (net (code "83") (name "/TRD1_N") (class "Default")
      (node (ref "J5") (pin "6") (pinfunction "TRD1N_6") (pintype "passive"))
      (node (ref "P2") (pin "2") (pinfunction "2_2") (pintype "passive"))
    )
    (net (code "84") (name "/TRD1_P") (class "Default")
      (node (ref "J5") (pin "4") (pinfunction "TRD1P_4") (pintype "passive"))
      (node (ref "P2") (pin "1") (pinfunction "1_1") (pintype "passive"))
    )
    (net (code "85") (name "/TRD2_N") (class "Default")
      (node (ref "J5") (pin "9") (pinfunction "TRD2N_9") (pintype "passive"))
      (node (ref "P1") (pin "5") (pinfunction "5_5") (pintype "passive"))
    )
    (net (code "86") (name "/TRD2_P") (class "Default")
      (node (ref "J5") (pin "11") (pinfunction "TRD2P_11") (pintype "passive"))
      (node (ref "P1") (pin "6") (pinfunction "6_6") (pintype "passive"))
    )
    (net (code "87") (name "/TRD3_N") (class "Default")
      (node (ref "J5") (pin "5") (pinfunction "TRD3N_5") (pintype "passive"))
      (node (ref "P1") (pin "4") (pinfunction "4_4") (pintype "passive"))
    )
    (net (code "88") (name "/TRD3_P") (class "Default")
      (node (ref "J5") (pin "3") (pinfunction "TRD3P_3") (pintype "passive"))
      (node (ref "P1") (pin "3") (pinfunction "3_3") (pintype "passive"))
    )
    (net (code "89") (name "/TXD0") (class "Default")
      (node (ref "J1") (pin "1") (pinfunction "1_1") (pintype "passive"))
      (node (ref "J5") (pin "55") (pinfunction "GPIO14_55") (pintype "passive"))
    )
    (net (code "90") (name "/USB_5V") (class "Default")
      (node (ref "J12") (pin "A4/B9") (pinfunction "VBUS_A4/B9") (pintype "passive"))
      (node (ref "J12") (pin "A9/B4") (pinfunction "VBUS_A9/B4") (pintype "passive"))
      (node (ref "R17") (pin "1") (pinfunction "1_1") (pintype "passive"))
      (node (ref "R20") (pin "1") (pinfunction "1_1") (pintype "passive"))
    )
    (net (code "91") (name "/USB_CC1") (class "Default")
      (node (ref "J12") (pin "A5") (pinfunction "CC1_A5") (pintype "passive"))
      (node (ref "R114") (pin "1") (pinfunction "1_1") (pintype "passive"))
    )
    (net (code "92") (name "/USB_CC2") (class "Default")
      (node (ref "J12") (pin "B5") (pinfunction "CC2_B5") (pintype "passive"))
      (node (ref "R115") (pin "1") (pinfunction "1_1") (pintype "passive"))
    )
    (net (code "93") (name "/USB_N") (class "Default")
      (node (ref "D12") (pin "2") (pinfunction "D-_2") (pintype "passive"))
      (node (ref "J12") (pin "A7") (pinfunction "D-1_A7") (pintype "passive"))
      (node (ref "J12") (pin "B7") (pinfunction "D-2_B7") (pintype "passive"))
      (node (ref "J6") (pin "103") (pinfunction "USB2N_103") (pintype "passive"))
    )
    (net (code "94") (name "/USB_P") (class "Default")
      (node (ref "D12") (pin "1") (pinfunction "D+_1") (pintype "passive"))
      (node (ref "J12") (pin "A6") (pinfunction "D+1_A6") (pintype "passive"))
      (node (ref "J12") (pin "B6") (pinfunction "D+2_B6") (pintype "passive"))
      (node (ref "J6") (pin "105") (pinfunction "USB2P_105") (pintype "passive"))
    )
    (net (code "95") (name "/WL_DIS") (class "Default")
      (node (ref "J5") (pin "89") (pinfunction "WL_nDISABLE_89") (pintype "passive"))
      (node (ref "R122") (pin "2") (pinfunction "2_2") (pintype "passive"))
    )
    (net (code "96") (name "/nEXTRST") (class "Default")
      (node (ref "J5") (pin "100") (pinfunction "nEXTRST_100") (pintype "passive"))
    )
    (net (code "100") (name "GND") (class "Default")
      (node (ref "C164") (pin "1") (pinfunction "1_1") (pintype "passive"))
      (node (ref "C49") (pin "2") (pinfunction "2_2") (pintype "passive"))
      (node (ref "C50") (pin "2") (pinfunction "2_2") (pintype "passive"))
      (node (ref "C51") (pin "2") (pinfunction "2_2") (pintype "passive"))
      (node (ref "C52") (pin "2") (pinfunction "2_2") (pintype "passive"))
      (node (ref "C53") (pin "2") (pinfunction "2_2") (pintype "passive"))
      (node (ref "C54") (pin "2") (pinfunction "2_2") (pintype "passive"))
      (node (ref "C55") (pin "2") (pinfunction "2_2") (pintype "passive"))
      (node (ref "C56") (pin "2") (pinfunction "2_2") (pintype "passive"))
      (node (ref "C66") (pin "1") (pinfunction "1_1") (pintype "passive"))
      (node (ref "CO3") (pin "6") (pinfunction "VSS_6") (pintype "passive"))
      (node (ref "CO3") (pin "GND") (pinfunction "GND_GND") (pintype "passive"))
      (node (ref "D11") (pin "1") (pinfunction "Cathode_1") (pintype "passive"))
      (node (ref "D12") (pin "3") (pinfunction "GND_3") (pintype "power_in"))
      (node (ref "D14") (pin "1") (pinfunction "Cathode_1") (pintype "passive"))
      (node (ref "IC7") (pin "4") (pinfunction "GND_4") (pintype "passive"))
      (node (ref "IC8") (pin "2") (pinfunction "GND_2") (pintype "power_in"))
      (node (ref "J1") (pin "3") (pinfunction "3_3") (pintype "passive"))
      (node (ref "J12") (pin "A1/B12") (pinfunction "GND_A1/B12") (pintype "passive"))
      (node (ref "J12") (pin "A12/B1") (pinfunction "GND_A12/B1") (pintype "passive"))
      (node (ref "J12") (pin "Shell") (pinfunction "Shield_Shell") (pintype "passive"))
      (node (ref "J2") (pin "2") (pinfunction "2_2") (pintype "passive"))
      (node (ref "J5") (pin "1") (pinfunction "GND_1") (pintype "passive"))
      (node (ref "J5") (pin "13") (pinfunction "GND_13") (pintype "passive"))
      (node (ref "J5") (pin "14") (pinfunction "GND_14") (pintype "passive"))
      (node (ref "J5") (pin "2") (pinfunction "GND_2") (pintype "passive"))
      (node (ref "J5") (pin "22") (pinfunction "GND_22") (pintype "passive"))
      (node (ref "J5") (pin "23") (pinfunction "GND_23") (pintype "passive"))
      (node (ref "J5") (pin "32") (pinfunction "GND_32") (pintype "passive"))
      (node (ref "J5") (pin "33") (pinfunction "GND_33") (pintype "passive"))
      (node (ref "J5") (pin "42") (pinfunction "GND_42") (pintype "passive"))
      (node (ref "J5") (pin "43") (pinfunction "GND_43") (pintype "passive"))
      (node (ref "J5") (pin "52") (pinfunction "GND_52") (pintype "passive"))
      (node (ref "J5") (pin "53") (pinfunction "GND_53") (pintype "passive"))
      (node (ref "J5") (pin "59") (pinfunction "GND_59") (pintype "passive"))
      (node (ref "J5") (pin "60") (pinfunction "GND_60") (pintype "passive"))
      (node (ref "J5") (pin "65") (pinfunction "GND_65") (pintype "passive"))
      (node (ref "J5") (pin "66") (pinfunction "GND_66") (pintype "passive"))
      (node (ref "J5") (pin "7") (pinfunction "GND_7") (pintype "passive"))
      (node (ref "J5") (pin "71") (pinfunction "GND_71") (pintype "passive"))
      (node (ref "J5") (pin "74") (pinfunction "GND_74") (pintype "passive"))
      (node (ref "J5") (pin "8") (pinfunction "GND_8") (pintype "passive"))
      (node (ref "J5") (pin "98") (pinfunction "GND_98") (pintype "passive"))
      (node (ref "J6") (pin "107") (pinfunction "GND_107") (pintype "passive"))
      (node (ref "J6") (pin "108") (pinfunction "GND_108") (pintype "passive"))
      (node (ref "J6") (pin "113") (pinfunction "GND_113") (pintype "passive"))
      (node (ref "J6") (pin "114") (pinfunction "GND_114") (pintype "passive"))
      (node (ref "J6") (pin "119") (pinfunction "GND_119") (pintype "passive"))
      (node (ref "J6") (pin "120") (pinfunction "GND_120") (pintype "passive"))
      (node (ref "J6") (pin "125") (pinfunction "GND_125") (pintype "passive"))
      (node (ref "J6") (pin "126") (pinfunction "GND_126") (pintype "passive"))
      (node (ref "J6") (pin "131") (pinfunction "GND_131") (pintype "passive"))
      (node (ref "J6") (pin "132") (pinfunction "GND_132") (pintype "passive"))
      (node (ref "J6") (pin "137") (pinfunction "GND_137") (pintype "passive"))
      (node (ref "J6") (pin "138") (pinfunction "GND_138") (pintype "passive"))
      (node (ref "J6") (pin "144") (pinfunction "GND_144") (pintype "passive"))
      (node (ref "J6") (pin "150") (pinfunction "GND_150") (pintype "passive"))
      (node (ref "J6") (pin "155") (pinfunction "GND_155") (pintype "passive"))
      (node (ref "J6") (pin "156") (pinfunction "GND_156") (pintype "passive"))
      (node (ref "J6") (pin "161") (pinfunction "GND_161") (pintype "passive"))
      (node (ref "J6") (pin "162") (pinfunction "GND_162") (pintype "passive"))
      (node (ref "J6") (pin "167") (pinfunction "GND_167") (pintype "passive"))
      (node (ref "J6") (pin "168") (pinfunction "GND_168") (pintype "passive"))
      (node (ref "J6") (pin "173") (pinfunction "GND_173") (pintype "passive"))
      (node (ref "J6") (pin "174") (pinfunction "GND_174") (pintype "passive"))
      (node (ref "J6") (pin "179") (pinfunction "GND_179") (pintype "passive"))
      (node (ref "J6") (pin "180") (pinfunction "GND_180") (pintype "passive"))
      (node (ref "J6") (pin "185") (pinfunction "GND_185") (pintype "passive"))
      (node (ref "J6") (pin "186") (pinfunction "GND_186") (pintype "passive"))
      (node (ref "J6") (pin "191") (pinfunction "GND_191") (pintype "passive"))
      (node (ref "J6") (pin "192") (pinfunction "GND_192") (pintype "passive"))
      (node (ref "J6") (pin "197") (pinfunction "GND_197") (pintype "passive"))
      (node (ref "J6") (pin "198") (pinfunction "GND_198") (pintype "passive"))
      (node (ref "J7") (pin "4") (pinfunction "4_4") (pintype "passive"))
      (node (ref "J8") (pin "5") (pinfunction "GND_5") (pintype "power_in"))
      (node (ref "P1") (pin "2") (pinfunction "2_2") (pintype "passive"))
      (node (ref "R114") (pin "2") (pinfunction "2_2") (pintype "passive"))
      (node (ref "R115") (pin "2") (pinfunction "2_2") (pintype "passive"))
      (node (ref "R122") (pin "1") (pinfunction "1_1") (pintype "passive"))
      (node (ref "R123") (pin "1") (pinfunction "1_1") (pintype "passive"))
      (node (ref "R124") (pin "1") (pinfunction "1_1") (pintype "passive"))
      (node (ref "R18") (pin "2") (pinfunction "2_2") (pintype "passive"))
      (node (ref "R224") (pin "1") (pinfunction "1_1") (pintype "passive"))
      (node (ref "U4") (pin "3") (pinfunction "GND_3") (pintype "power_in"))
      (node (ref "U8") (pin "4") (pinfunction "GND_4") (pintype "power_in"))
      (node (ref "X2") (pin "10") (pinfunction "10_10") (pintype "passive"))
      (node (ref "X2") (pin "9") (pinfunction "9_9") (pintype "passive"))
    )
    (net (code "101") (name "Net-(CO3-VDD)") (class "Default")
      (node (ref "C54") (pin "1") (pinfunction "1_1") (pintype "passive"))
      (node (ref "CO3") (pin "4") (pinfunction "VDD_4") (pintype "passive"))
      (node (ref "IC8") (pin "1") (pinfunction "Vout_1") (pintype "power_in"))
    )
    (net (code "102") (name "Net-(D10-Anode)") (class "Default")
      (node (ref "D10") (pin "2") (pinfunction "Anode_2") (pintype "passive"))
      (node (ref "R19") (pin "1") (pinfunction "1_1") (pintype "passive"))
    )
    (net (code "103") (name "Net-(D10-Cathode)") (class "Default")
      (node (ref "D10") (pin "1") (pinfunction "Cathode_1") (pintype "passive"))
      (node (ref "J5") (pin "21") (pinfunction "PI_nLED_ACT_21") (pintype "passive"))
    )
    (net (code "104") (name "Net-(D11-Anode)") (class "Default")
      (node (ref "D11") (pin "2") (pinfunction "Anode_2") (pintype "passive"))
      (node (ref "R20") (pin "2") (pinfunction "2_2") (pintype "passive"))
    )
    (net (code "105") (name "Net-(D13-Cathode)") (class "Default")
      (node (ref "D13") (pin "1") (pinfunction "Cathode_1") (pintype "passive"))
      (node (ref "R125") (pin "2") (pinfunction "2_2") (pintype "passive"))
    )
    (net (code "106") (name "Net-(D14-Anode)") (class "Default")
      (node (ref "D14") (pin "2") (pinfunction "Anode_2") (pintype "passive"))
      (node (ref "R126") (pin "2") (pinfunction "2_2") (pintype "passive"))
    )
    (net (code "107") (name "Net-(IC7-PWM)") (class "Default")
      (node (ref "IC7") (pin "5") (pinfunction "PWM_5") (pintype "passive"))
      (node (ref "J7") (pin "1") (pinfunction "1_1") (pintype "passive"))
    )
    (net (code "108") (name "Net-(IC7-TACH)") (class "Default")
      (node (ref "IC7") (pin "6") (pinfunction "TACH_6") (pintype "passive"))
      (node (ref "J7") (pin "2") (pinfunction "2_2") (pintype "passive"))
      (node (ref "R121") (pin "2") (pinfunction "2_2") (pintype "passive"))
    )
    (net (code "109") (name "Net-(U4-Y)") (class "Default")
      (node (ref "R125") (pin "1") (pinfunction "1_1") (pintype "passive"))
      (node (ref "U4") (pin "4") (pinfunction "Y_4") (pintype "output"))
    )
    (net (code "110") (name "unconnected-(CO3-PadCD)") (class "Default")
      (node (ref "CO3") (pin "CD") (pinfunction "CD_CD") (pintype "passive"))
    )
    (net (code "111") (name "unconnected-(IC7-ALERT#-Pad8)") (class "Default")
      (node (ref "IC7") (pin "8") (pinfunction "ALERT#_8") (pintype "passive"))
    )
    (net (code "112") (name "unconnected-(IC7-CLK-Pad7)") (class "Default")
      (node (ref "IC7") (pin "7") (pinfunction "CLK_7") (pintype "passive"))
    )
    (net (code "113") (name "unconnected-(IC8-FLG-Pad3)") (class "Default")
      (node (ref "IC8") (pin "3") (pinfunction "FLG_3") (pintype "power_in"))
    )
    (net (code "114") (name "unconnected-(J5-+1.8V_OUT-Pad88)") (class "Default")
      (node (ref "J5") (pin "88") (pinfunction "+1.8V_OUT_88") (pintype "passive"))
    )
    (net (code "115") (name "unconnected-(J5-+1.8V_OUT-Pad90)") (class "Default")
      (node (ref "J5") (pin "90") (pinfunction "+1.8V_OUT_90") (pintype "passive"))
    )
    (net (code "116") (name "unconnected-(J5-+5V_IN-Pad77)") (class "Default")
      (node (ref "J5") (pin "77") (pinfunction "+5V_IN_77") (pintype "passive"))
    )
    (net (code "117") (name "unconnected-(J5-AIN0-Pad96)") (class "Default")
      (node (ref "J5") (pin "96") (pinfunction "AIN0_96") (pintype "passive"))
    )
    (net (code "118") (name "unconnected-(J5-AIN1-Pad94)") (class "Default")
      (node (ref "J5") (pin "94") (pinfunction "AIN1_94") (pintype "passive"))
    )
    (net (code "119") (name "unconnected-(J5-CAMERA_GPIO-Pad97)") (class "Default")
      (node (ref "J5") (pin "97") (pinfunction "CAMERA_GPIO_97") (pintype "passive"))
    )
    (net (code "120") (name "unconnected-(J5-GPIO13-Pad28)") (class "Default")
      (node (ref "J5") (pin "28") (pinfunction "GPIO13_28") (pintype "passive"))
    )
    (net (code "121") (name "unconnected-(J5-GPIO22-Pad46)") (class "Default")
      (node (ref "J5") (pin "46") (pinfunction "GPIO22_46") (pintype "passive"))
    )
    (net (code "122") (name "unconnected-(J5-GPIO23-Pad47)") (class "Default")
      (node (ref "J5") (pin "47") (pinfunction "GPIO23_47") (pintype "passive"))
    )
    (net (code "123") (name "unconnected-(J5-GPIO26-Pad24)") (class "Default")
      (node (ref "J5") (pin "24") (pinfunction "GPIO26_24") (pintype "passive"))
    )
    (net (code "124") (name "unconnected-(J5-GPIO27-Pad48)") (class "Default")
      (node (ref "J5") (pin "48") (pinfunction "GPIO27_48") (pintype "passive"))
    )
    (net (code "125") (name "unconnected-(J5-ID_SC-Pad35)") (class "Default")
      (node (ref "J5") (pin "35") (pinfunction "ID_SC_35") (pintype "passive"))
    )
    (net (code "126") (name "unconnected-(J5-ID_SD-Pad36)") (class "Default")
      (node (ref "J5") (pin "36") (pinfunction "ID_SD_36") (pintype "passive"))
    )
    (net (code "127") (name "unconnected-(J5-NC-Pad19)") (class "Default")
      (node (ref "J5") (pin "19") (pinfunction "NC_19") (pintype "passive"))
    )
    (net (code "128") (name "unconnected-(J5-Reserved-Pad76)") (class "Default")
      (node (ref "J5") (pin "76") (pinfunction "Reserved_76") (pintype "passive"))
    )
    (net (code "129") (name "unconnected-(J5-SD_DAT4-Pad68)") (class "Default")
      (node (ref "J5") (pin "68") (pinfunction "SD_DAT4_68") (pintype "passive"))
    )
    (net (code "130") (name "unconnected-(J5-SD_DAT5-Pad64)") (class "Default")
      (node (ref "J5") (pin "64") (pinfunction "SD_DAT5_64") (pintype "passive"))
    )
    (net (code "131") (name "unconnected-(J5-SD_DAT6-Pad72)") (class "Default")
      (node (ref "J5") (pin "72") (pinfunction "SD_DAT6_72") (pintype "passive"))
    )
    (net (code "132") (name "unconnected-(J5-SD_DAT7-Pad70)") (class "Default")
      (node (ref "J5") (pin "70") (pinfunction "SD_DAT7_70") (pintype "passive"))
    )
    (net (code "133") (name "unconnected-(J5-SD_VDD_OVER-Pad73)") (class "Default")
      (node (ref "J5") (pin "73") (pinfunction "SD_VDD_OVER_73") (pintype "passive"))
    )
    (net (code "134") (name "unconnected-(J5-SYNC_IN(1.8V)-Pad16)") (class "Default")
      (node (ref "J5") (pin "16") (pinfunction "SYNC_IN(1.8V)_16") (pintype "passive"))
    )
    (net (code "135") (name "unconnected-(J5-SYNC_OUT(1.8V)-Pad18)") (class "Default")
      (node (ref "J5") (pin "18") (pinfunction "SYNC_OUT(1.8V)_18") (pintype "passive"))
    )
    (net (code "136") (name "unconnected-(J6-CAM0_C_N-Pad140)") (class "Default")
      (node (ref "J6") (pin "140") (pinfunction "CAM0_C_N_140") (pintype "passive"))
    )
    (net (code "137") (name "unconnected-(J6-CAM0_C_P-Pad142)") (class "Default")
      (node (ref "J6") (pin "142") (pinfunction "CAM0_C_P_142") (pintype "passive"))
    )
    (net (code "138") (name "unconnected-(J6-CAM0_D0_N-Pad128)") (class "Default")
      (node (ref "J6") (pin "128") (pinfunction "CAM0_D0_N_128") (pintype "passive"))
    )
    (net (code "139") (name "unconnected-(J6-CAM0_D0_P-Pad130)") (class "Default")
      (node (ref "J6") (pin "130") (pinfunction "CAM0_D0_P_130") (pintype "passive"))
    )
    (net (code "140") (name "unconnected-(J6-CAM0_D1_N-Pad134)") (class "Default")
      (node (ref "J6") (pin "134") (pinfunction "CAM0_D1_N_134") (pintype "passive"))
    )
    (net (code "141") (name "unconnected-(J6-CAM0_D1_P-Pad136)") (class "Default")
      (node (ref "J6") (pin "136") (pinfunction "CAM0_D1_P_136") (pintype "passive"))
    )
    (net (code "142") (name "unconnected-(J6-CAM1_C_N-Pad127)") (class "Default")
      (node (ref "J6") (pin "127") (pinfunction "CAM1_C_N_127") (pintype "passive"))
    )
    (net (code "143") (name "unconnected-(J6-CAM1_C_P-Pad129)") (class "Default")
      (node (ref "J6") (pin "129") (pinfunction "CAM1_C_P_129") (pintype "passive"))
    )
    (net (code "144") (name "unconnected-(J6-CAM1_D0_N-Pad115)") (class "Default")
      (node (ref "J6") (pin "115") (pinfunction "CAM1_D0_N_115") (pintype "passive"))
    )
    (net (code "145") (name "unconnected-(J6-CAM1_D0_P-Pad117)") (class "Default")
      (node (ref "J6") (pin "117") (pinfunction "CAM1_D0_P_117") (pintype "passive"))
    )
    (net (code "146") (name "unconnected-(J6-CAM1_D1_N-Pad121)") (class "Default")
      (node (ref "J6") (pin "121") (pinfunction "CAM1_D1_N_121") (pintype "passive"))
    )
    (net (code "147") (name "unconnected-(J6-CAM1_D1_P-Pad123)") (class "Default")
      (node (ref "J6") (pin "123") (pinfunction "CAM1_D1_P_123") (pintype "passive"))
    )
    (net (code "148") (name "unconnected-(J6-CAM1_D2_N-Pad133)") (class "Default")
      (node (ref "J6") (pin "133") (pinfunction "CAM1_D2_N_133") (pintype "passive"))
    )
    (net (code "149") (name "unconnected-(J6-CAM1_D2_P-Pad135)") (class "Default")
      (node (ref "J6") (pin "135") (pinfunction "CAM1_D2_P_135") (pintype "passive"))
    )
    (net (code "150") (name "unconnected-(J6-CAM1_D3_N-Pad139)") (class "Default")
      (node (ref "J6") (pin "139") (pinfunction "CAM1_D3_N_139") (pintype "passive"))
    )
    (net (code "151") (name "unconnected-(J6-CAM1_D3_P-Pad141)") (class "Default")
      (node (ref "J6") (pin "141") (pinfunction "CAM1_D3_P_141") (pintype "passive"))
    )
    (net (code "152") (name "unconnected-(J6-DSI0_C_N-Pad169)") (class "Default")
      (node (ref "J6") (pin "169") (pinfunction "DSI0_C_N_169") (pintype "passive"))
    )
    (net (code "153") (name "unconnected-(J6-DSI0_C_P-Pad171)") (class "Default")
      (node (ref "J6") (pin "171") (pinfunction "DSI0_C_P_171") (pintype "passive"))
    )
    (net (code "154") (name "unconnected-(J6-DSI0_D0_N-Pad157)") (class "Default")
      (node (ref "J6") (pin "157") (pinfunction "DSI0_D0_N_157") (pintype "passive"))
    )
    (net (code "155") (name "unconnected-(J6-DSI0_D0_P-Pad159)") (class "Default")
      (node (ref "J6") (pin "159") (pinfunction "DSI0_D0_P_159") (pintype "passive"))
    )
    (net (code "156") (name "unconnected-(J6-DSI0_D1_N-Pad163)") (class "Default")
      (node (ref "J6") (pin "163") (pinfunction "DSI0_D1_N_163") (pintype "passive"))
    )
    (net (code "157") (name "unconnected-(J6-DSI0_D1_P-Pad165)") (class "Default")
      (node (ref "J6") (pin "165") (pinfunction "DSI0_D1_P_165") (pintype "passive"))
    )
    (net (code "158") (name "unconnected-(J6-DSI1_C_N-Pad187)") (class "Default")
      (node (ref "J6") (pin "187") (pinfunction "DSI1_C_N_187") (pintype "passive"))
    )
    (net (code "159") (name "unconnected-(J6-DSI1_C_P-Pad189)") (class "Default")
      (node (ref "J6") (pin "189") (pinfunction "DSI1_C_P_189") (pintype "passive"))
    )
    (net (code "160") (name "unconnected-(J6-DSI1_D0_N-Pad175)") (class "Default")
      (node (ref "J6") (pin "175") (pinfunction "DSI1_D0_N_175") (pintype "passive"))
    )
    (net (code "161") (name "unconnected-(J6-DSI1_D0_P-Pad177)") (class "Default")
      (node (ref "J6") (pin "177") (pinfunction "DSI1_D0_P_177") (pintype "passive"))
    )
    (net (code "162") (name "unconnected-(J6-DSI1_D1_N-Pad181)") (class "Default")
      (node (ref "J6") (pin "181") (pinfunction "DSI1_D1_N_181") (pintype "passive"))
    )
    (net (code "163") (name "unconnected-(J6-DSI1_D1_P-Pad183)") (class "Default")
      (node (ref "J6") (pin "183") (pinfunction "DSI1_D1_P_183") (pintype "passive"))
    )
    (net (code "164") (name "unconnected-(J6-DSI1_D2_N-Pad193)") (class "Default")
      (node (ref "J6") (pin "193") (pinfunction "DSI1_D2_N_193") (pintype "passive"))
    )
    (net (code "165") (name "unconnected-(J6-DSI1_D2_P-Pad195)") (class "Default")
      (node (ref "J6") (pin "195") (pinfunction "DSI1_D2_P_195") (pintype "passive"))
    )
    (net (code "166") (name "unconnected-(J6-DSI1_D3_N-Pad194)") (class "Default")
      (node (ref "J6") (pin "194") (pinfunction "DSI1_D3_N_194") (pintype "passive"))
    )
    (net (code "167") (name "unconnected-(J6-DSI1_D3_P-Pad196)") (class "Default")
      (node (ref "J6") (pin "196") (pinfunction "DSI1_D3_P_196") (pintype "passive"))
    )
    (net (code "168") (name "unconnected-(J6-Reserved-Pad104)") (class "Default")
      (node (ref "J6") (pin "104") (pinfunction "Reserved_104") (pintype "passive"))
    )
    (net (code "169") (name "unconnected-(J6-Reserved-Pad106)") (class "Default")
      (node (ref "J6") (pin "106") (pinfunction "Reserved_106") (pintype "passive"))
    )
    (net (code "170") (name "unconnected-(J6-VDAC_COMP-Pad111)") (class "Default")
      (node (ref "J6") (pin "111") (pinfunction "VDAC_COMP_111") (pintype "passive"))
    )
    (net (code "171") (name "unconnected-(J12-SBU1-PadA8)") (class "Default")
      (node (ref "J12") (pin "A8") (pinfunction "SBU1_A8") (pintype "passive"))
    )
    (net (code "172") (name "unconnected-(J12-SBU2-PadB8)") (class "Default")
      (node (ref "J12") (pin "B8") (pinfunction "SBU2_B8") (pintype "passive"))
    )
    (net (code "173") (name "unconnected-(U4-NC-Pad1)") (class "Default")
      (node (ref "U4") (pin "1") (pinfunction "NC_1") (pintype "passive+no_connect"))
    )
  )
)
